# SwitchDemoWing.net
KiCad netlist of a schematic drawn in EAGLE
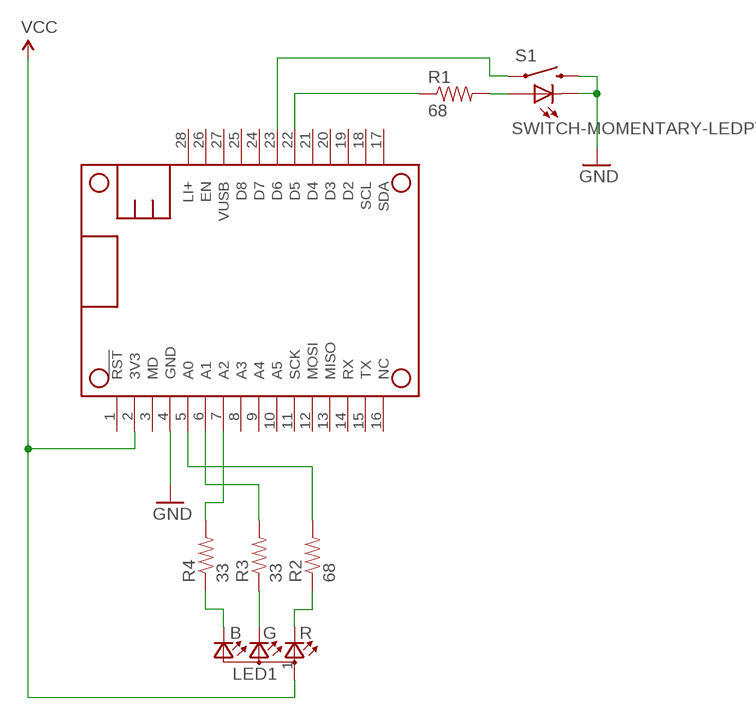
[diagram p0: schematic, sheet 1]

(export (version "E")
  (design (tool "Eeschema 10.0.6"))
  (components
    (comp (ref "LED1")
      (value "LED-RGB-CREE-SMD")
      (footprint "eagle-import:LED-RGB-CREE-SMD")
      (libsource (lib "eagle-import") (part "LED-RGB-CREE-SMD"))
    )
    (comp (ref "MS1")
      (value "PARTICLE_MESH_NODIM")
      (footprint "eagle-import:FEATHERWING_NODIM")
      (libsource (lib "eagle-import") (part "PARTICLE_MESH_NODIM"))
    )
    (comp (ref "R1")
      (value "68")
      (footprint "eagle-import:0603-RES")
      (libsource (lib "eagle-import") (part "RES-68-0603.DEV"))
    )
    (comp (ref "R2")
      (value "68")
      (footprint "eagle-import:0603-RES")
      (libsource (lib "eagle-import") (part "RES-68-0603.DEV"))
    )
    (comp (ref "R3")
      (value "33")
      (footprint "eagle-import:0603-RES")
      (libsource (lib "eagle-import") (part "RES-33-0603.DEV"))
    )
    (comp (ref "R4")
      (value "33")
      (footprint "eagle-import:0603-RES")
      (libsource (lib "eagle-import") (part "RES-33-0603.DEV"))
    )
    (comp (ref "S1")
      (value "SWITCH-MOMENTARY-LEDPTH")
      (footprint "eagle-import:TACTILE-PTH-LED-12MM")
      (libsource (lib "eagle-import") (part "SWITCH-MOMENTARY-LEDPTH"))
    )
  )
  (nets
    (net (code "1") (name "/LI+") (class "Default")
      (node (ref "MS1") (pin "28") (pinfunction "LI+_28") (pintype "power_in"))
    )
    (net (code "2") (name "/VUSB") (class "Default")
      (node (ref "MS1") (pin "27") (pinfunction "VUSB_27") (pintype "power_in"))
    )
    (net (code "3") (name "GND") (class "Default")
      (node (ref "MS1") (pin "4") (pinfunction "GND_4") (pintype "power_in"))
      (node (ref "S1") (pin "2") (pinfunction "2_2") (pintype "passive"))
      (node (ref "S1") (pin "C") (pinfunction "C_C") (pintype "passive"))
    )
    (net (code "4") (name "Net-(LED1-B)") (class "Default")
      (node (ref "LED1") (pin "2") (pinfunction "B_2") (pintype "passive"))
      (node (ref "R4") (pin "1") (pinfunction "1_1") (pintype "passive"))
    )
    (net (code "5") (name "Net-(LED1-G)") (class "Default")
      (node (ref "LED1") (pin "3") (pinfunction "G_3") (pintype "passive"))
      (node (ref "R3") (pin "1") (pinfunction "1_1") (pintype "passive"))
    )
    (net (code "6") (name "Net-(LED1-R)") (class "Default")
      (node (ref "LED1") (pin "4") (pinfunction "R_4") (pintype "passive"))
      (node (ref "R2") (pin "1") (pinfunction "1_1") (pintype "passive"))
    )
    (net (code "7") (name "Net-(MS1-A0)") (class "Default")
      (node (ref "MS1") (pin "5") (pinfunction "A0_5") (pintype "bidirectional"))
      (node (ref "R2") (pin "2") (pinfunction "2_2") (pintype "passive"))
    )
    (net (code "8") (name "Net-(MS1-A1)") (class "Default")
      (node (ref "MS1") (pin "6") (pinfunction "A1_6") (pintype "bidirectional"))
      (node (ref "R3") (pin "2") (pinfunction "2_2") (pintype "passive"))
    )
    (net (code "9") (name "Net-(MS1-A2)") (class "Default")
      (node (ref "MS1") (pin "7") (pinfunction "A2_7") (pintype "bidirectional"))
      (node (ref "R4") (pin "2") (pinfunction "2_2") (pintype "passive"))
    )
    (net (code "10") (name "Net-(MS1-D5)") (class "Default")
      (node (ref "MS1") (pin "22") (pinfunction "D5_22") (pintype "bidirectional"))
      (node (ref "R1") (pin "1") (pinfunction "1_1") (pintype "passive"))
    )
    (net (code "11") (name "Net-(MS1-D6)") (class "Default")
      (node (ref "MS1") (pin "23") (pinfunction "D6_23") (pintype "bidirectional"))
      (node (ref "S1") (pin "4") (pinfunction "1_4") (pintype "passive"))
    )
    (net (code "12") (name "Net-(R1-Pad2)") (class "Default")
      (node (ref "R1") (pin "2") (pinfunction "2_2") (pintype "passive"))
      (node (ref "S1") (pin "A") (pinfunction "A_A") (pintype "passive"))
    )
    (net (code "13") (name "VCC") (class "Default")
      (node (ref "LED1") (pin "1") (pinfunction "A_1") (pintype "passive"))
      (node (ref "MS1") (pin "2") (pinfunction "3V3_2") (pintype "power_in"))
    )
    (net (code "14") (name "unconnected-(MS1-A3-Pad8)") (class "Default")
      (node (ref "MS1") (pin "8") (pinfunction "A3_8") (pintype "bidirectional"))
    )
    (net (code "15") (name "unconnected-(MS1-A4-Pad9)") (class "Default")
      (node (ref "MS1") (pin "9") (pinfunction "A4_9") (pintype "bidirectional"))
    )
    (net (code "16") (name "unconnected-(MS1-A5-Pad10)") (class "Default")
      (node (ref "MS1") (pin "10") (pinfunction "A5_10") (pintype "bidirectional"))
    )
    (net (code "17") (name "unconnected-(MS1-D2-Pad19)") (class "Default")
      (node (ref "MS1") (pin "19") (pinfunction "D2_19") (pintype "bidirectional"))
    )
    (net (code "18") (name "unconnected-(MS1-D3-Pad20)") (class "Default")
      (node (ref "MS1") (pin "20") (pinfunction "D3_20") (pintype "bidirectional"))
    )
    (net (code "19") (name "unconnected-(MS1-D4-Pad21)") (class "Default")
      (node (ref "MS1") (pin "21") (pinfunction "D4_21") (pintype "bidirectional"))
    )
    (net (code "20") (name "unconnected-(MS1-D7-Pad24)") (class "Default")
      (node (ref "MS1") (pin "24") (pinfunction "D7_24") (pintype "bidirectional"))
    )
    (net (code "21") (name "unconnected-(MS1-D8-Pad25)") (class "Default")
      (node (ref "MS1") (pin "25") (pinfunction "D8_25") (pintype "bidirectional"))
    )
    (net (code "22") (name "unconnected-(MS1-EN-Pad26)") (class "Default")
      (node (ref "MS1") (pin "26") (pinfunction "EN_26") (pintype "passive"))
    )
    (net (code "23") (name "unconnected-(MS1-MD-Pad3)") (class "Default")
      (node (ref "MS1") (pin "3") (pinfunction "MD_3") (pintype "bidirectional"))
    )
    (net (code "24") (name "unconnected-(MS1-MISO-Pad13)") (class "Default")
      (node (ref "MS1") (pin "13") (pinfunction "MISO_13") (pintype "bidirectional"))
    )
    (net (code "25") (name "unconnected-(MS1-MOSI-Pad12)") (class "Default")
      (node (ref "MS1") (pin "12") (pinfunction "MOSI_12") (pintype "bidirectional"))
    )
    (net (code "26") (name "unconnected-(MS1-NC-Pad16)") (class "Default")
      (node (ref "MS1") (pin "16") (pinfunction "NC_16") (pintype "passive"))
    )
    (net (code "27") (name "unconnected-(MS1-RX-Pad14)") (class "Default")
      (node (ref "MS1") (pin "14") (pinfunction "RX_14") (pintype "bidirectional"))
    )
    (net (code "28") (name "unconnected-(MS1-SCK-Pad11)") (class "Default")
      (node (ref "MS1") (pin "11") (pinfunction "SCK_11") (pintype "bidirectional"))
    )
    (net (code "29") (name "unconnected-(MS1-SCL-Pad18)") (class "Default")
      (node (ref "MS1") (pin "18") (pinfunction "SCL_18") (pintype "bidirectional"))
    )
    (net (code "30") (name "unconnected-(MS1-SDA-Pad17)") (class "Default")
      (node (ref "MS1") (pin "17") (pinfunction "SDA_17") (pintype "bidirectional"))
    )
    (net (code "31") (name "unconnected-(MS1-TX-Pad15)") (class "Default")
      (node (ref "MS1") (pin "15") (pinfunction "TX_15") (pintype "bidirectional"))
    )
    (net (code "32") (name "unconnected-(MS1-~{RST}-Pad1)") (class "Default")
      (node (ref "MS1") (pin "1") (pinfunction "~{RST}_1") (pintype "input"))
    )
  )
)
